# NODE_MCU_ESP12.net
KiCad netlist of a schematic drawn in Altium Designer
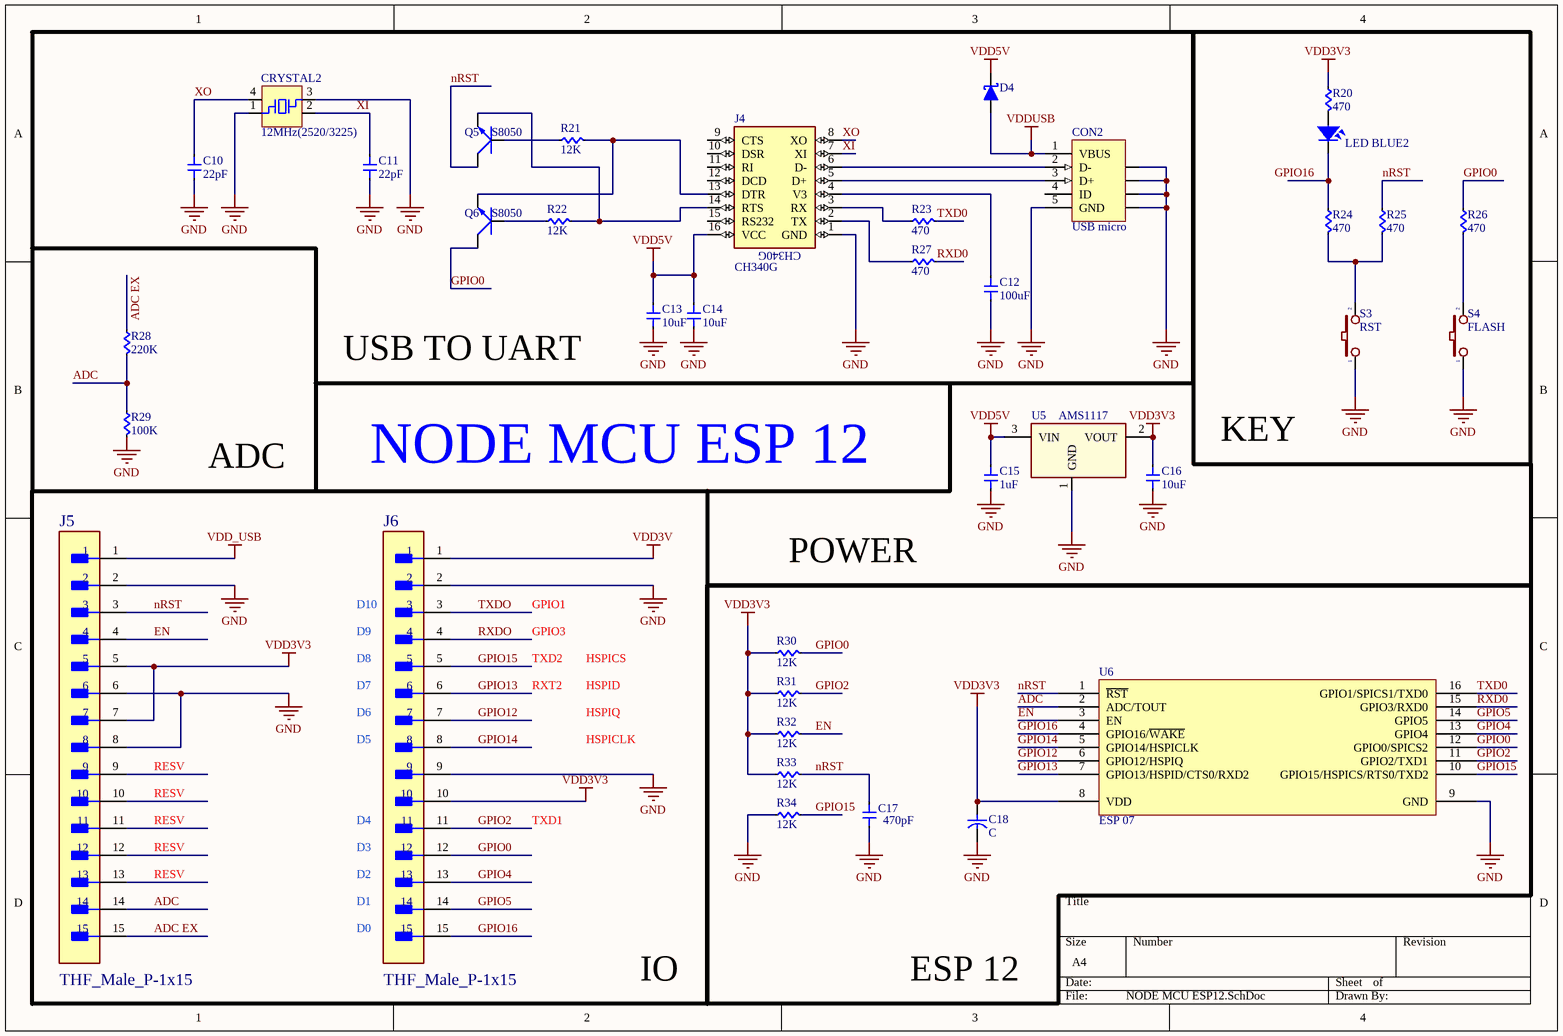
[diagram p0: NODE MCU ESP12.SchDoc]

(export (version "E")
  (design (tool "Eeschema 10.0.6"))
  (components
    (comp (ref "C10")
      (value "22pF")
      (footprint "Cap 0201")
      (description "Capacitor SMD 0201")
      (libsource (lib "Altium_Lib_by_KhueNguyenCreator") (part "Cap 0201"))
    )
    (comp (ref "C11")
      (value "22pF")
      (footprint "Cap 0201")
      (description "Capacitor SMD 0201")
      (libsource (lib "Altium_Lib_by_KhueNguyenCreator") (part "Cap 0201"))
    )
    (comp (ref "C12")
      (value "100uF")
      (footprint "Cap 0201")
      (description "Capacitor SMD 0201")
      (libsource (lib "Altium_Lib_by_KhueNguyenCreator") (part "Cap 0201"))
    )
    (comp (ref "C13")
      (value "10uF")
      (footprint "Cap 0201")
      (description "Capacitor SMD 0201")
      (libsource (lib "Altium_Lib_by_KhueNguyenCreator") (part "Cap 0201"))
    )
    (comp (ref "C14")
      (value "10uF")
      (footprint "Cap 0201")
      (description "Capacitor SMD 0201")
      (libsource (lib "Altium_Lib_by_KhueNguyenCreator") (part "Cap 0201"))
    )
    (comp (ref "C15")
      (value "1uF")
      (footprint "Cap 0201")
      (description "Capacitor SMD 0201")
      (libsource (lib "Altium_Lib_by_KhueNguyenCreator") (part "Cap 0201"))
    )
    (comp (ref "C16")
      (value "10uF")
      (footprint "Cap 0201")
      (description "Capacitor SMD 0201")
      (libsource (lib "Altium_Lib_by_KhueNguyenCreator") (part "Cap 0201"))
    )
    (comp (ref "C17")
      (value "470pF")
      (footprint "Cap 1210")
      (description "Capacitor SMD 1210")
      (libsource (lib "Altium_Lib_by_KhueNguyenCreator") (part "Cap 1210"))
    )
    (comp (ref "C18")
      (value "C")
      (footprint "C SMD TAN 1210 (B)")
      (description "Capacitor pol")
      (libsource (lib "chipfc_altium_libs") (part "Capacitor"))
    )
    (comp (ref "CON2")
      (value "USB micro")
      (footprint "CONN/USB/MICRO/RA")
      (description "USB micro, 5 pins")
      (libsource (lib "chipfc_altium_libs") (part "CON USB micro"))
    )
    (comp (ref "CRYSTAL2")
      (value "12MHz(2520/3225)")
      (footprint "Crystal SMD 4PIN 32x25")
      (libsource (lib "chipfc_altium_libs") (part "Crystal 4pin"))
    )
    (comp (ref "D4")
      (value "~")
      (footprint "DO-214AC (SMA)")
      (description "Schottky Diode")
      (libsource (lib "chipfc_altium_libs") (part "Diode Schottky"))
    )
    (comp (ref "J4")
      (value "CH340G")
      (footprint "SOIC-16")
      (description "USB Interface Integrated Circuit")
      (fields (field (name "MP") "Ch340G") (field (name "MF") "WCH"))
      (libsource (lib "chipfc_altium_libs") (part "CH340G"))
    )
    (comp (ref "J5")
      (value "THF_Male_P-1x15")
      (footprint "FP-90121-0135-MFG")
      (description "CONN HEADER R/A 15POS 2.54MM")
      (libsource (lib "Components - 26.03.25 - 00.08") (part "CMP-04776-000526-1"))
    )
    (comp (ref "J6")
      (value "THF_Male_P-1x15")
      (footprint "FP-90121-0135-MFG")
      (description "CONN HEADER R/A 15POS 2.54MM")
      (libsource (lib "Components - 26.03.25 - 00.08") (part "CMP-04776-000526-1"))
    )
    (comp (ref "LED BLUE2")
      (value "LED")
      (footprint "LED-5-BLUE")
      (description "LED Single colour Green and Red")
      (libsource (lib "LIBRARY") (part "LED"))
    )
    (comp (ref "Q5")
      (value "S8050")
      (footprint "TO92")
      (description "NPN transistor EBC")
      (libsource (lib "Altium_Lib_by_KhueNguyenCreator") (part "Trans 2N3904"))
    )
    (comp (ref "Q6")
      (value "S8050")
      (footprint "TO92")
      (description "NPN transistor EBC")
      (libsource (lib "Altium_Lib_by_KhueNguyenCreator") (part "Trans 2N3904"))
    )
    (comp (ref "R20")
      (value "470")
      (footprint "RES 0402")
      (description "RES SMD 0402")
      (fields
        (field (name "MANUFACTURER") "Vishay Dale")
        (field (name "MANUFACTURER PART NUMBER") "CRCW040210K0FKED")
      )
      (libsource (lib "Altium_Lib_by_KhueNguyenCreator") (part "RES 0402"))
    )
    (comp (ref "R21")
      (value "12K")
      (footprint "RES 0402")
      (description "RES SMD 0402")
      (fields
        (field (name "MANUFACTURER") "Vishay Dale")
        (field (name "MANUFACTURER PART NUMBER") "CRCW040210K0FKED")
      )
      (libsource (lib "Altium_Lib_by_KhueNguyenCreator") (part "RES 0402"))
    )
    (comp (ref "R22")
      (value "12K")
      (footprint "RES 0402")
      (description "RES SMD 0402")
      (fields
        (field (name "MANUFACTURER") "Vishay Dale")
        (field (name "MANUFACTURER PART NUMBER") "CRCW040210K0FKED")
      )
      (libsource (lib "Altium_Lib_by_KhueNguyenCreator") (part "RES 0402"))
    )
    (comp (ref "R23")
      (value "470")
      (footprint "RES 0402")
      (description "RES SMD 0402")
      (fields
        (field (name "MANUFACTURER") "Vishay Dale")
        (field (name "MANUFACTURER PART NUMBER") "CRCW040210K0FKED")
      )
      (libsource (lib "Altium_Lib_by_KhueNguyenCreator") (part "RES 0402"))
    )
    (comp (ref "R24")
      (value "470")
      (footprint "RES 0402")
      (description "RES SMD 0402")
      (fields
        (field (name "MANUFACTURER") "Vishay Dale")
        (field (name "MANUFACTURER PART NUMBER") "CRCW040210K0FKED")
      )
      (libsource (lib "Altium_Lib_by_KhueNguyenCreator") (part "RES 0402"))
    )
    (comp (ref "R25")
      (value "470")
      (footprint "RES 0402")
      (description "RES SMD 0402")
      (fields
        (field (name "MANUFACTURER") "Vishay Dale")
        (field (name "MANUFACTURER PART NUMBER") "CRCW040210K0FKED")
      )
      (libsource (lib "Altium_Lib_by_KhueNguyenCreator") (part "RES 0402"))
    )
    (comp (ref "R26")
      (value "470")
      (footprint "RES 0402")
      (description "RES SMD 0402")
      (fields
        (field (name "MANUFACTURER") "Vishay Dale")
        (field (name "MANUFACTURER PART NUMBER") "CRCW040210K0FKED")
      )
      (libsource (lib "Altium_Lib_by_KhueNguyenCreator") (part "RES 0402"))
    )
    (comp (ref "R27")
      (value "470")
      (footprint "RES 0402")
      (description "RES SMD 0402")
      (fields
        (field (name "MANUFACTURER") "Vishay Dale")
        (field (name "MANUFACTURER PART NUMBER") "CRCW040210K0FKED")
      )
      (libsource (lib "Altium_Lib_by_KhueNguyenCreator") (part "RES 0402"))
    )
    (comp (ref "R28")
      (value "220K")
      (footprint "RES 0402")
      (description "RES SMD 0402")
      (fields
        (field (name "MANUFACTURER") "Vishay Dale")
        (field (name "MANUFACTURER PART NUMBER") "CRCW040210K0FKED")
      )
      (libsource (lib "Altium_Lib_by_KhueNguyenCreator") (part "RES 0402"))
    )
    (comp (ref "R29")
      (value "100K")
      (footprint "RES 0402")
      (description "RES SMD 0402")
      (fields
        (field (name "MANUFACTURER") "Vishay Dale")
        (field (name "MANUFACTURER PART NUMBER") "CRCW040210K0FKED")
      )
      (libsource (lib "Altium_Lib_by_KhueNguyenCreator") (part "RES 0402"))
    )
    (comp (ref "R30")
      (value "12K")
      (footprint "RES 0402")
      (description "RES SMD 0402")
      (fields
        (field (name "MANUFACTURER") "Vishay Dale")
        (field (name "MANUFACTURER PART NUMBER") "CRCW040210K0FKED")
      )
      (libsource (lib "Altium_Lib_by_KhueNguyenCreator") (part "RES 0402"))
    )
    (comp (ref "R31")
      (value "12K")
      (footprint "RES 0402")
      (description "RES SMD 0402")
      (fields
        (field (name "MANUFACTURER") "Vishay Dale")
        (field (name "MANUFACTURER PART NUMBER") "CRCW040210K0FKED")
      )
      (libsource (lib "Altium_Lib_by_KhueNguyenCreator") (part "RES 0402"))
    )
    (comp (ref "R32")
      (value "12K")
      (footprint "RES 0402")
      (description "RES SMD 0402")
      (fields
        (field (name "MANUFACTURER") "Vishay Dale")
        (field (name "MANUFACTURER PART NUMBER") "CRCW040210K0FKED")
      )
      (libsource (lib "Altium_Lib_by_KhueNguyenCreator") (part "RES 0402"))
    )
    (comp (ref "R33")
      (value "12K")
      (footprint "RES 0402")
      (description "RES SMD 0402")
      (fields
        (field (name "MANUFACTURER") "Vishay Dale")
        (field (name "MANUFACTURER PART NUMBER") "CRCW040210K0FKED")
      )
      (libsource (lib "Altium_Lib_by_KhueNguyenCreator") (part "RES 0402"))
    )
    (comp (ref "R34")
      (value "12K")
      (footprint "RES 0402")
      (description "RES SMD 0402")
      (fields
        (field (name "MANUFACTURER") "Vishay Dale")
        (field (name "MANUFACTURER PART NUMBER") "CRCW040210K0FKED")
      )
      (libsource (lib "Altium_Lib_by_KhueNguyenCreator") (part "RES 0402"))
    )
    (comp (ref "S3")
      (value "RST")
      (footprint "SW1-SMD")
      (description "Switch button 2 pin")
      (libsource (lib "LIBRARY") (part "SW2"))
    )
    (comp (ref "S4")
      (value "FLASH")
      (footprint "SW1-SMD")
      (description "Switch button 2 pin")
      (libsource (lib "LIBRARY") (part "SW2"))
    )
    (comp (ref "U5")
      (value "AMS1117")
      (footprint "SOT-223")
      (description "1A LDO Voltage Regulator, ADJ or fixed 1.5/1.8/2.5/2.85/3.3/5V")
      (libsource (lib "chipfc_altium_libs") (part "AMS1117"))
    )
    (comp (ref "U6")
      (value "ESP 07")
      (footprint "ESP8266 07")
      (description "ESP8266 07 16 Pin")
      (libsource (lib "Altium_Lib_by_KhueNguyenCreator") (part "ESP8266 07"))
    )
  )
  (nets
    (net (code "1") (name "/ADC") (class "Default")
      (node (ref "J5") (pin "14") (pinfunction "14_14") (pintype "passive"))
      (node (ref "R28") (pin "2") (pinfunction "2_2") (pintype "passive"))
      (node (ref "R29") (pin "1") (pinfunction "1_1") (pintype "passive"))
      (node (ref "U6") (pin "2") (pinfunction "ADC/TOUT_2") (pintype "passive"))
    )
    (net (code "2") (name "/ADC EX") (class "Default")
      (node (ref "J5") (pin "15") (pinfunction "15_15") (pintype "passive"))
      (node (ref "R28") (pin "1") (pinfunction "1_1") (pintype "passive"))
    )
    (net (code "14") (name "/EN") (class "Default")
      (node (ref "J5") (pin "4") (pinfunction "4_4") (pintype "passive"))
      (node (ref "R32") (pin "2") (pinfunction "2_2") (pintype "passive"))
      (node (ref "U6") (pin "3") (pinfunction "EN_3") (pintype "passive"))
    )
    (net (code "15") (name "/GPIO0") (class "Default")
      (node (ref "J6") (pin "12") (pinfunction "12_12") (pintype "passive"))
      (node (ref "Q6") (pin "3") (pinfunction "C_3") (pintype "passive"))
      (node (ref "R26") (pin "1") (pinfunction "1_1") (pintype "passive"))
      (node (ref "R30") (pin "2") (pinfunction "2_2") (pintype "passive"))
      (node (ref "U6") (pin "12") (pinfunction "GPIO0/SPICS2_12") (pintype "passive"))
    )
    (net (code "16") (name "/GPIO1") (class "Default")
      (node (ref "J6") (pin "3") (pinfunction "3_3") (pintype "passive"))
    )
    (net (code "17") (name "/GPIO2") (class "Default")
      (node (ref "J6") (pin "11") (pinfunction "11_11") (pintype "passive"))
      (node (ref "R31") (pin "2") (pinfunction "2_2") (pintype "passive"))
      (node (ref "U6") (pin "11") (pinfunction "GPIO2/TXD1_11") (pintype "passive"))
    )
    (net (code "18") (name "/GPIO3") (class "Default")
      (node (ref "J6") (pin "4") (pinfunction "4_4") (pintype "passive"))
    )
    (net (code "19") (name "/GPIO4") (class "Default")
      (node (ref "J6") (pin "13") (pinfunction "13_13") (pintype "passive"))
      (node (ref "U6") (pin "13") (pinfunction "GPIO4_13") (pintype "passive"))
    )
    (net (code "20") (name "/GPIO5") (class "Default")
      (node (ref "J6") (pin "14") (pinfunction "14_14") (pintype "passive"))
      (node (ref "U6") (pin "14") (pinfunction "GPIO5_14") (pintype "passive"))
    )
    (net (code "21") (name "/GPIO12") (class "Default")
      (node (ref "J6") (pin "7") (pinfunction "7_7") (pintype "passive"))
      (node (ref "U6") (pin "6") (pinfunction "GPIO12/HSPIQ_6") (pintype "passive"))
    )
    (net (code "22") (name "/GPIO13") (class "Default")
      (node (ref "J6") (pin "6") (pinfunction "6_6") (pintype "passive"))
      (node (ref "U6") (pin "7") (pinfunction "GPIO13/HSPID/CTS0/RXD2_7") (pintype "passive"))
    )
    (net (code "23") (name "/GPIO14") (class "Default")
      (node (ref "J6") (pin "8") (pinfunction "8_8") (pintype "passive"))
      (node (ref "U6") (pin "5") (pinfunction "GPIO14/HSPICLK_5") (pintype "passive"))
    )
    (net (code "24") (name "/GPIO15") (class "Default")
      (node (ref "J6") (pin "5") (pinfunction "5_5") (pintype "passive"))
      (node (ref "R34") (pin "2") (pinfunction "2_2") (pintype "passive"))
      (node (ref "U6") (pin "10") (pinfunction "GPIO15/HSPICS/RTS0/TXD2_10") (pintype "passive"))
    )
    (net (code "25") (name "/GPIO16") (class "Default")
      (node (ref "J6") (pin "15") (pinfunction "15_15") (pintype "passive"))
      (node (ref "U6") (pin "4") (pinfunction "GPIO16/~{WAKE}_4") (pintype "passive"))
    )
    (net (code "30") (name "/RESV") (class "Default")
      (node (ref "J5") (pin "10") (pinfunction "10_10") (pintype "passive"))
      (node (ref "J5") (pin "11") (pinfunction "11_11") (pintype "passive"))
      (node (ref "J5") (pin "12") (pinfunction "12_12") (pintype "passive"))
      (node (ref "J5") (pin "13") (pinfunction "13_13") (pintype "passive"))
      (node (ref "J5") (pin "9") (pinfunction "9_9") (pintype "passive"))
    )
    (net (code "31") (name "/RXD0") (class "Default")
      (node (ref "R27") (pin "2") (pinfunction "2_2") (pintype "passive"))
      (node (ref "U6") (pin "15") (pinfunction "GPIO3/RXD0_15") (pintype "passive"))
    )
    (net (code "32") (name "/TXD0") (class "Default")
      (node (ref "R23") (pin "2") (pinfunction "2_2") (pintype "passive"))
      (node (ref "U6") (pin "16") (pinfunction "GPIO1/SPICS1/TXD0_16") (pintype "passive"))
    )
    (net (code "33") (name "/XI") (class "Default")
      (node (ref "C11") (pin "2") (pinfunction "2_2") (pintype "passive"))
      (node (ref "CRYSTAL2") (pin "2") (pinfunction "GND_2") (pintype "passive"))
      (node (ref "J4") (pin "7") (pinfunction "XI_7") (pintype "bidirectional"))
    )
    (net (code "34") (name "/XO") (class "Default")
      (node (ref "C10") (pin "2") (pinfunction "2_2") (pintype "passive"))
      (node (ref "CRYSTAL2") (pin "4") (pinfunction "GND_4") (pintype "passive"))
      (node (ref "J4") (pin "8") (pinfunction "XO_8") (pintype "bidirectional"))
    )
    (net (code "35") (name "/nRST") (class "Default")
      (node (ref "C17") (pin "2") (pinfunction "2_2") (pintype "passive"))
      (node (ref "J5") (pin "3") (pinfunction "3_3") (pintype "passive"))
      (node (ref "Q5") (pin "3") (pinfunction "C_3") (pintype "passive"))
      (node (ref "R25") (pin "1") (pinfunction "1_1") (pintype "passive"))
      (node (ref "R33") (pin "2") (pinfunction "2_2") (pintype "passive"))
      (node (ref "U6") (pin "1") (pinfunction "~{RST}_1") (pintype "passive"))
    )
    (net (code "36") (name "GND") (class "Default")
      (node (ref "C10") (pin "1") (pinfunction "1_1") (pintype "passive"))
      (node (ref "C11") (pin "1") (pinfunction "1_1") (pintype "passive"))
      (node (ref "C12") (pin "1") (pinfunction "1_1") (pintype "passive"))
      (node (ref "C13") (pin "1") (pinfunction "1_1") (pintype "passive"))
      (node (ref "C14") (pin "1") (pinfunction "1_1") (pintype "passive"))
      (node (ref "C15") (pin "1") (pinfunction "1_1") (pintype "passive"))
      (node (ref "C16") (pin "1") (pinfunction "1_1") (pintype "passive"))
      (node (ref "C17") (pin "1") (pinfunction "1_1") (pintype "passive"))
      (node (ref "C18") (pin "2") (pinfunction "2_2") (pintype "passive"))
      (node (ref "CON2") (pin "5") (pinfunction "GND_5") (pintype "power_in"))
      (node (ref "CON2") (pin "6") (pinfunction "SHLD_6") (pintype "passive"))
      (node (ref "CON2") (pin "7") (pinfunction "SHLD_7") (pintype "passive"))
      (node (ref "CON2") (pin "8") (pinfunction "SHLD_8") (pintype "passive"))
      (node (ref "CON2") (pin "9") (pinfunction "SHLD_9") (pintype "passive"))
      (node (ref "CRYSTAL2") (pin "1") (pinfunction "XTAL_1") (pintype "passive"))
      (node (ref "CRYSTAL2") (pin "3") (pinfunction "XTAL_3") (pintype "passive"))
      (node (ref "J4") (pin "1") (pinfunction "GND_1") (pintype "bidirectional"))
      (node (ref "J5") (pin "2") (pinfunction "2_2") (pintype "passive"))
      (node (ref "J5") (pin "6") (pinfunction "6_6") (pintype "passive"))
      (node (ref "J5") (pin "8") (pinfunction "8_8") (pintype "passive"))
      (node (ref "J6") (pin "2") (pinfunction "2_2") (pintype "passive"))
      (node (ref "J6") (pin "9") (pinfunction "9_9") (pintype "passive"))
      (node (ref "R29") (pin "2") (pinfunction "2_2") (pintype "passive"))
      (node (ref "R34") (pin "1") (pinfunction "1_1") (pintype "passive"))
      (node (ref "S3") (pin "1") (pinfunction "1_1") (pintype "passive"))
      (node (ref "S4") (pin "1") (pinfunction "1_1") (pintype "passive"))
      (node (ref "U5") (pin "1") (pinfunction "GND_1") (pintype "passive"))
      (node (ref "U6") (pin "9") (pinfunction "GND_9") (pintype "passive"))
    )
    (net (code "37") (name "Net-(CON2-D+)") (class "Default")
      (node (ref "CON2") (pin "3") (pinfunction "D+_3") (pintype "input"))
      (node (ref "J4") (pin "5") (pinfunction "D+_5") (pintype "bidirectional"))
    )
    (net (code "38") (name "Net-(CON2-D-)") (class "Default")
      (node (ref "CON2") (pin "2") (pinfunction "D-_2") (pintype "input"))
      (node (ref "J4") (pin "6") (pinfunction "D-_6") (pintype "bidirectional"))
    )
    (net (code "39") (name "Net-(J4-DTR)") (class "Default")
      (node (ref "J4") (pin "13") (pinfunction "DTR_13") (pintype "bidirectional"))
      (node (ref "Q6") (pin "1") (pinfunction "E_1") (pintype "passive"))
      (node (ref "R21") (pin "2") (pinfunction "2_2") (pintype "passive"))
    )
    (net (code "40") (name "Net-(J4-RTS)") (class "Default")
      (node (ref "J4") (pin "14") (pinfunction "RTS_14") (pintype "bidirectional"))
      (node (ref "Q5") (pin "1") (pinfunction "E_1") (pintype "passive"))
      (node (ref "R22") (pin "2") (pinfunction "2_2") (pintype "passive"))
    )
    (net (code "41") (name "Net-(J4-RX)") (class "Default")
      (node (ref "J4") (pin "3") (pinfunction "RX_3") (pintype "bidirectional"))
      (node (ref "R23") (pin "1") (pinfunction "1_1") (pintype "passive"))
    )
    (net (code "42") (name "Net-(J4-TX)") (class "Default")
      (node (ref "J4") (pin "2") (pinfunction "TX_2") (pintype "bidirectional"))
      (node (ref "R27") (pin "1") (pinfunction "1_1") (pintype "passive"))
    )
    (net (code "43") (name "Net-(J4-V3)") (class "Default")
      (node (ref "C12") (pin "2") (pinfunction "2_2") (pintype "passive"))
      (node (ref "J4") (pin "4") (pinfunction "V3_4") (pintype "bidirectional"))
    )
    (net (code "44") (name "Net-(LED BLUE2-Pad1)") (class "Default")
      (node (ref "LED BLUE2") (pin "1") (pinfunction "1_1") (pintype "passive"))
      (node (ref "R20") (pin "2") (pinfunction "2_2") (pintype "passive"))
    )
    (net (code "45") (name "Net-(LED BLUE2-Pad2)") (class "Default")
      (node (ref "LED BLUE2") (pin "2") (pinfunction "2_2") (pintype "passive"))
      (node (ref "R24") (pin "1") (pinfunction "1_1") (pintype "passive"))
    )
    (net (code "46") (name "Net-(Q5-B)") (class "Default")
      (node (ref "Q5") (pin "2") (pinfunction "B_2") (pintype "passive"))
      (node (ref "R21") (pin "1") (pinfunction "1_1") (pintype "passive"))
    )
    (net (code "47") (name "Net-(Q6-B)") (class "Default")
      (node (ref "Q6") (pin "2") (pinfunction "B_2") (pintype "passive"))
      (node (ref "R22") (pin "1") (pinfunction "1_1") (pintype "passive"))
    )
    (net (code "48") (name "Net-(R24-Pad2)") (class "Default")
      (node (ref "R24") (pin "2") (pinfunction "2_2") (pintype "passive"))
      (node (ref "R25") (pin "2") (pinfunction "2_2") (pintype "passive"))
      (node (ref "S3") (pin "2") (pinfunction "2_2") (pintype "passive"))
    )
    (net (code "49") (name "Net-(R26-Pad2)") (class "Default")
      (node (ref "R26") (pin "2") (pinfunction "2_2") (pintype "passive"))
      (node (ref "S4") (pin "2") (pinfunction "2_2") (pintype "passive"))
    )
    (net (code "50") (name "VDD3V") (class "Default")
      (node (ref "J6") (pin "1") (pinfunction "1_1") (pintype "passive"))
    )
    (net (code "51") (name "VDD3V3") (class "Default")
      (node (ref "C16") (pin "2") (pinfunction "2_2") (pintype "passive"))
      (node (ref "C18") (pin "1") (pinfunction "1_1") (pintype "passive"))
      (node (ref "J5") (pin "5") (pinfunction "5_5") (pintype "passive"))
      (node (ref "J5") (pin "7") (pinfunction "7_7") (pintype "passive"))
      (node (ref "J6") (pin "10") (pinfunction "10_10") (pintype "passive"))
      (node (ref "R20") (pin "1") (pinfunction "1_1") (pintype "passive"))
      (node (ref "R30") (pin "1") (pinfunction "1_1") (pintype "passive"))
      (node (ref "R31") (pin "1") (pinfunction "1_1") (pintype "passive"))
      (node (ref "R32") (pin "1") (pinfunction "1_1") (pintype "passive"))
      (node (ref "R33") (pin "1") (pinfunction "1_1") (pintype "passive"))
      (node (ref "U5") (pin "2") (pinfunction "VOUT_2") (pintype "passive"))
      (node (ref "U6") (pin "8") (pinfunction "VDD_8") (pintype "passive"))
    )
    (net (code "52") (name "VDD5V") (class "Default")
      (node (ref "C13") (pin "2") (pinfunction "2_2") (pintype "passive"))
      (node (ref "C14") (pin "2") (pinfunction "2_2") (pintype "passive"))
      (node (ref "C15") (pin "2") (pinfunction "2_2") (pintype "passive"))
      (node (ref "D4") (pin "2") (pinfunction "K_2") (pintype "passive"))
      (node (ref "J4") (pin "16") (pinfunction "VCC_16") (pintype "bidirectional"))
      (node (ref "U5") (pin "3") (pinfunction "VIN_3") (pintype "power_in"))
    )
    (net (code "53") (name "VDDUSB") (class "Default")
      (node (ref "CON2") (pin "1") (pinfunction "VBUS_1") (pintype "power_in"))
      (node (ref "D4") (pin "1") (pinfunction "A_1") (pintype "passive"))
    )
    (net (code "54") (name "VDD_USB") (class "Default")
      (node (ref "J5") (pin "1") (pinfunction "1_1") (pintype "passive"))
    )
    (net (code "55") (name "unconnected-(CON2-ID-Pad4)") (class "Default")
      (node (ref "CON2") (pin "4") (pinfunction "ID_4") (pintype "passive"))
    )
    (net (code "56") (name "unconnected-(J4-CTS-Pad9)") (class "Default")
      (node (ref "J4") (pin "9") (pinfunction "CTS_9") (pintype "bidirectional"))
    )
    (net (code "57") (name "unconnected-(J4-DCD-Pad12)") (class "Default")
      (node (ref "J4") (pin "12") (pinfunction "DCD_12") (pintype "bidirectional"))
    )
    (net (code "58") (name "unconnected-(J4-DSR-Pad10)") (class "Default")
      (node (ref "J4") (pin "10") (pinfunction "DSR_10") (pintype "bidirectional"))
    )
    (net (code "59") (name "unconnected-(J4-RI-Pad11)") (class "Default")
      (node (ref "J4") (pin "11") (pinfunction "RI_11") (pintype "bidirectional"))
    )
    (net (code "60") (name "unconnected-(J4-RS232-Pad15)") (class "Default")
      (node (ref "J4") (pin "15") (pinfunction "RS232_15") (pintype "bidirectional"))
    )
  )
)
